# Back_Drill_Example.net
KiCad netlist of a schematic drawn in Altium Designer
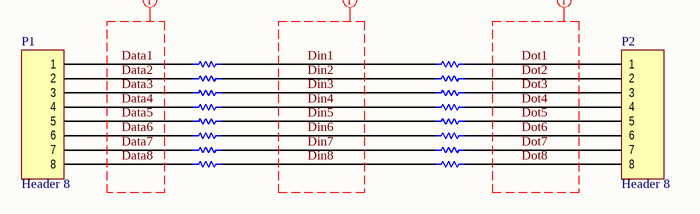
[diagram p0:  Back Drill Example.SchDoc]

(export (version "E")
  (design (tool "Eeschema 10.0.6"))
  (components
    (comp (ref "P1")
      (value "Header 8")
      (footprint "HDR1X8")
      (description "Header, 8-Pin")
      (fields (field (name "PUBLISHER") "Altium Limited"))
      (libsource (lib "Miscellaneous Connectors") (part "Header 8"))
    )
    (comp (ref "P2")
      (value "Header 8")
      (footprint "HDR1X8")
      (description "Header, 8-Pin")
      (fields (field (name "PUBLISHER") "Altium Limited"))
      (libsource (lib "") (part "Header 8_1"))
    )
    (comp (ref "R1")
      (value "1K 0603")
      (footprint "0603_L")
      (fields
        (field (name "MANUFACTURER") "Panasonic Electronic Components")
        (field (name "MANUFACTURER PART NUMBER") "ERJ-3GEYJ102V")
        (field (name "TOLERANCE") "±5%")
      )
      (libsource (lib "WCTopping") (part "Res1K_0603"))
    )
    (comp (ref "R2")
      (value "1K 0603")
      (footprint "0603_L")
      (fields
        (field (name "MANUFACTURER") "Panasonic Electronic Components")
        (field (name "MANUFACTURER PART NUMBER") "ERJ-3GEYJ102V")
        (field (name "TOLERANCE") "±5%")
      )
      (libsource (lib "WCTopping") (part "Res1K_0603"))
    )
    (comp (ref "R3")
      (value "1K 0603")
      (footprint "0603_L")
      (fields
        (field (name "MANUFACTURER") "Panasonic Electronic Components")
        (field (name "MANUFACTURER PART NUMBER") "ERJ-3GEYJ102V")
        (field (name "TOLERANCE") "±5%")
      )
      (libsource (lib "WCTopping") (part "Res1K_0603"))
    )
    (comp (ref "R4")
      (value "1K 0603")
      (footprint "0603_L")
      (fields
        (field (name "MANUFACTURER") "Panasonic Electronic Components")
        (field (name "MANUFACTURER PART NUMBER") "ERJ-3GEYJ102V")
        (field (name "TOLERANCE") "±5%")
      )
      (libsource (lib "WCTopping") (part "Res1K_0603"))
    )
    (comp (ref "R5")
      (value "1K 0603")
      (footprint "0603_L")
      (fields
        (field (name "MANUFACTURER") "Panasonic Electronic Components")
        (field (name "MANUFACTURER PART NUMBER") "ERJ-3GEYJ102V")
        (field (name "TOLERANCE") "±5%")
      )
      (libsource (lib "WCTopping") (part "Res1K_0603"))
    )
    (comp (ref "R6")
      (value "1K 0603")
      (footprint "0603_L")
      (fields
        (field (name "MANUFACTURER") "Panasonic Electronic Components")
        (field (name "MANUFACTURER PART NUMBER") "ERJ-3GEYJ102V")
        (field (name "TOLERANCE") "±5%")
      )
      (libsource (lib "WCTopping") (part "Res1K_0603"))
    )
    (comp (ref "R7")
      (value "1K 0603")
      (footprint "0603_L")
      (fields
        (field (name "MANUFACTURER") "Panasonic Electronic Components")
        (field (name "MANUFACTURER PART NUMBER") "ERJ-3GEYJ102V")
        (field (name "TOLERANCE") "±5%")
      )
      (libsource (lib "WCTopping") (part "Res1K_0603"))
    )
    (comp (ref "R8")
      (value "1K 0603")
      (footprint "0603_L")
      (fields
        (field (name "MANUFACTURER") "Panasonic Electronic Components")
        (field (name "MANUFACTURER PART NUMBER") "ERJ-3GEYJ102V")
        (field (name "TOLERANCE") "±5%")
      )
      (libsource (lib "WCTopping") (part "Res1K_0603"))
    )
    (comp (ref "RS1")
      (value "1K 0603")
      (footprint "0603_L")
      (fields
        (field (name "MANUFACTURER") "Panasonic Electronic Components")
        (field (name "MANUFACTURER PART NUMBER") "ERJ-3GEYJ102V")
        (field (name "TOLERANCE") "±5%")
      )
      (libsource (lib "WCTopping") (part "Res1K_0603"))
    )
    (comp (ref "RS2")
      (value "1K 0603")
      (footprint "0603_L")
      (fields
        (field (name "MANUFACTURER") "Panasonic Electronic Components")
        (field (name "MANUFACTURER PART NUMBER") "ERJ-3GEYJ102V")
        (field (name "TOLERANCE") "±5%")
      )
      (libsource (lib "WCTopping") (part "Res1K_0603"))
    )
    (comp (ref "RS3")
      (value "1K 0603")
      (footprint "0603_L")
      (fields
        (field (name "MANUFACTURER") "Panasonic Electronic Components")
        (field (name "MANUFACTURER PART NUMBER") "ERJ-3GEYJ102V")
        (field (name "TOLERANCE") "±5%")
      )
      (libsource (lib "WCTopping") (part "Res1K_0603"))
    )
    (comp (ref "RS4")
      (value "1K 0603")
      (footprint "0603_L")
      (fields
        (field (name "MANUFACTURER") "Panasonic Electronic Components")
        (field (name "MANUFACTURER PART NUMBER") "ERJ-3GEYJ102V")
        (field (name "TOLERANCE") "±5%")
      )
      (libsource (lib "WCTopping") (part "Res1K_0603"))
    )
    (comp (ref "RS5")
      (value "1K 0603")
      (footprint "0603_L")
      (fields
        (field (name "MANUFACTURER") "Panasonic Electronic Components")
        (field (name "MANUFACTURER PART NUMBER") "ERJ-3GEYJ102V")
        (field (name "TOLERANCE") "±5%")
      )
      (libsource (lib "WCTopping") (part "Res1K_0603"))
    )
    (comp (ref "RS6")
      (value "1K 0603")
      (footprint "0603_L")
      (fields
        (field (name "MANUFACTURER") "Panasonic Electronic Components")
        (field (name "MANUFACTURER PART NUMBER") "ERJ-3GEYJ102V")
        (field (name "TOLERANCE") "±5%")
      )
      (libsource (lib "WCTopping") (part "Res1K_0603"))
    )
    (comp (ref "RS7")
      (value "1K 0603")
      (footprint "0603_L")
      (fields
        (field (name "MANUFACTURER") "Panasonic Electronic Components")
        (field (name "MANUFACTURER PART NUMBER") "ERJ-3GEYJ102V")
        (field (name "TOLERANCE") "±5%")
      )
      (libsource (lib "WCTopping") (part "Res1K_0603"))
    )
    (comp (ref "RS8")
      (value "1K 0603")
      (footprint "0603_L")
      (fields
        (field (name "MANUFACTURER") "Panasonic Electronic Components")
        (field (name "MANUFACTURER PART NUMBER") "ERJ-3GEYJ102V")
        (field (name "TOLERANCE") "±5%")
      )
      (libsource (lib "WCTopping") (part "Res1K_0603"))
    )
  )
  (nets
    (net (code "1") (name "/Data1") (class "Default")
      (node (ref "P1") (pin "1") (pinfunction "1_1") (pintype "passive"))
      (node (ref "R1") (pin "1") (pinfunction "1_1") (pintype "passive"))
    )
    (net (code "2") (name "/Data2") (class "Default")
      (node (ref "P1") (pin "2") (pinfunction "2_2") (pintype "passive"))
      (node (ref "R2") (pin "1") (pinfunction "1_1") (pintype "passive"))
    )
    (net (code "3") (name "/Data3") (class "Default")
      (node (ref "P1") (pin "3") (pinfunction "3_3") (pintype "passive"))
      (node (ref "R3") (pin "1") (pinfunction "1_1") (pintype "passive"))
    )
    (net (code "4") (name "/Data4") (class "Default")
      (node (ref "P1") (pin "4") (pinfunction "4_4") (pintype "passive"))
      (node (ref "R4") (pin "1") (pinfunction "1_1") (pintype "passive"))
    )
    (net (code "5") (name "/Data5") (class "Default")
      (node (ref "P1") (pin "5") (pinfunction "5_5") (pintype "passive"))
      (node (ref "R5") (pin "1") (pinfunction "1_1") (pintype "passive"))
    )
    (net (code "6") (name "/Data6") (class "Default")
      (node (ref "P1") (pin "6") (pinfunction "6_6") (pintype "passive"))
      (node (ref "R6") (pin "1") (pinfunction "1_1") (pintype "passive"))
    )
    (net (code "7") (name "/Data7") (class "Default")
      (node (ref "P1") (pin "7") (pinfunction "7_7") (pintype "passive"))
      (node (ref "R7") (pin "1") (pinfunction "1_1") (pintype "passive"))
    )
    (net (code "8") (name "/Data8") (class "Default")
      (node (ref "P1") (pin "8") (pinfunction "8_8") (pintype "passive"))
      (node (ref "R8") (pin "1") (pinfunction "1_1") (pintype "passive"))
    )
    (net (code "9") (name "/Din1") (class "Default")
      (node (ref "R1") (pin "2") (pinfunction "2_2") (pintype "passive"))
      (node (ref "RS1") (pin "1") (pinfunction "1_1") (pintype "passive"))
    )
    (net (code "10") (name "/Din2") (class "Default")
      (node (ref "R2") (pin "2") (pinfunction "2_2") (pintype "passive"))
      (node (ref "RS2") (pin "1") (pinfunction "1_1") (pintype "passive"))
    )
    (net (code "11") (name "/Din3") (class "Default")
      (node (ref "R3") (pin "2") (pinfunction "2_2") (pintype "passive"))
      (node (ref "RS3") (pin "1") (pinfunction "1_1") (pintype "passive"))
    )
    (net (code "12") (name "/Din4") (class "Default")
      (node (ref "R4") (pin "2") (pinfunction "2_2") (pintype "passive"))
      (node (ref "RS4") (pin "1") (pinfunction "1_1") (pintype "passive"))
    )
    (net (code "13") (name "/Din5") (class "Default")
      (node (ref "R5") (pin "2") (pinfunction "2_2") (pintype "passive"))
      (node (ref "RS5") (pin "1") (pinfunction "1_1") (pintype "passive"))
    )
    (net (code "14") (name "/Din6") (class "Default")
      (node (ref "R6") (pin "2") (pinfunction "2_2") (pintype "passive"))
      (node (ref "RS6") (pin "1") (pinfunction "1_1") (pintype "passive"))
    )
    (net (code "15") (name "/Din7") (class "Default")
      (node (ref "R7") (pin "2") (pinfunction "2_2") (pintype "passive"))
      (node (ref "RS7") (pin "1") (pinfunction "1_1") (pintype "passive"))
    )
    (net (code "16") (name "/Din8") (class "Default")
      (node (ref "R8") (pin "2") (pinfunction "2_2") (pintype "passive"))
      (node (ref "RS8") (pin "1") (pinfunction "1_1") (pintype "passive"))
    )
    (net (code "17") (name "/Dot1") (class "Default")
      (node (ref "P2") (pin "1") (pinfunction "1_1") (pintype "passive"))
      (node (ref "RS1") (pin "2") (pinfunction "2_2") (pintype "passive"))
    )
    (net (code "18") (name "/Dot2") (class "Default")
      (node (ref "P2") (pin "2") (pinfunction "2_2") (pintype "passive"))
      (node (ref "RS2") (pin "2") (pinfunction "2_2") (pintype "passive"))
    )
    (net (code "19") (name "/Dot3") (class "Default")
      (node (ref "P2") (pin "3") (pinfunction "3_3") (pintype "passive"))
      (node (ref "RS3") (pin "2") (pinfunction "2_2") (pintype "passive"))
    )
    (net (code "20") (name "/Dot4") (class "Default")
      (node (ref "P2") (pin "4") (pinfunction "4_4") (pintype "passive"))
      (node (ref "RS4") (pin "2") (pinfunction "2_2") (pintype "passive"))
    )
    (net (code "21") (name "/Dot5") (class "Default")
      (node (ref "P2") (pin "5") (pinfunction "5_5") (pintype "passive"))
      (node (ref "RS5") (pin "2") (pinfunction "2_2") (pintype "passive"))
    )
    (net (code "22") (name "/Dot6") (class "Default")
      (node (ref "P2") (pin "6") (pinfunction "6_6") (pintype "passive"))
      (node (ref "RS6") (pin "2") (pinfunction "2_2") (pintype "passive"))
    )
    (net (code "23") (name "/Dot7") (class "Default")
      (node (ref "P2") (pin "7") (pinfunction "7_7") (pintype "passive"))
      (node (ref "RS7") (pin "2") (pinfunction "2_2") (pintype "passive"))
    )
    (net (code "24") (name "/Dot8") (class "Default")
      (node (ref "P2") (pin "8") (pinfunction "8_8") (pintype "passive"))
      (node (ref "RS8") (pin "2") (pinfunction "2_2") (pintype "passive"))
    )
  )
)
